# SyncScan_Standalone_MK3_SMD.net
KiCad netlist of a schematic drawn in EAGLE
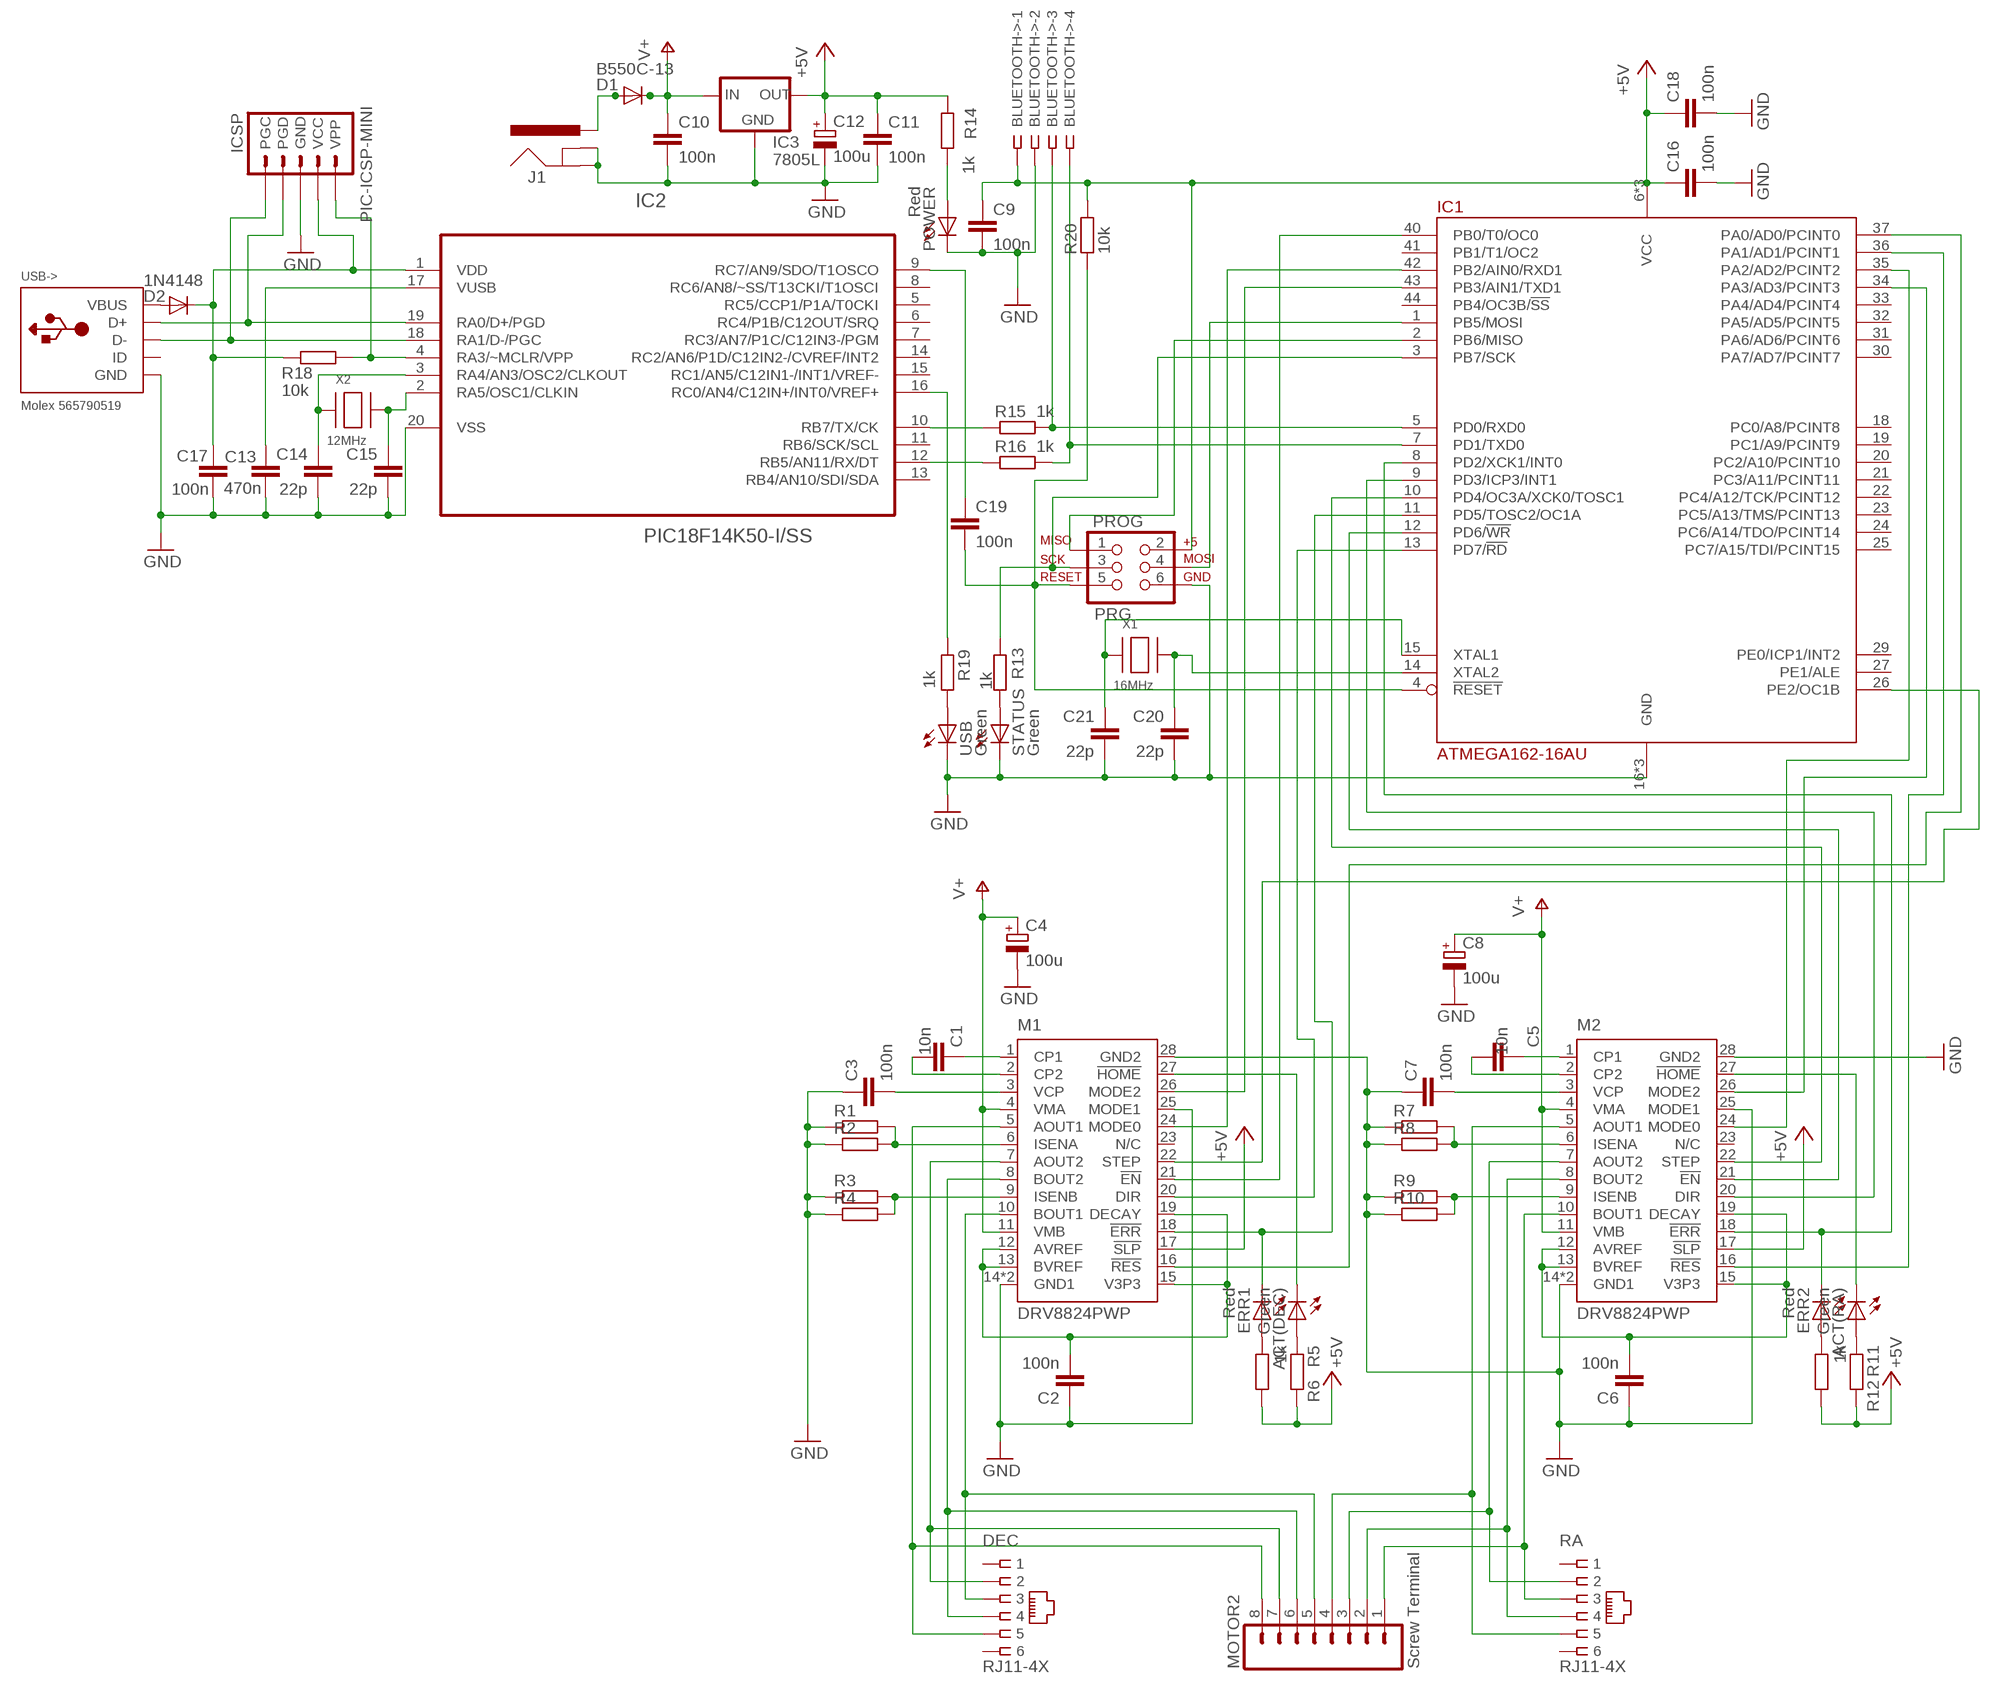
[diagram p0: schematic, sheet 1]

(export (version "E")
  (design (tool "Eeschema 10.0.6"))
  (components
    (comp (ref "ACT(DEC)")
      (value "Green")
      (footprint "eagle-import:1206")
      (fields (field (name "MF") "KINGBRIGHT") (field (name "MPN") "L-424GDT"))
      (libsource (lib "eagle-import") (part "LEDSMT1206"))
    )
    (comp (ref "ACT(RA)")
      (value "Green")
      (footprint "eagle-import:1206")
      (fields (field (name "MF") "KINGBRIGHT") (field (name "MPN") "L-424GDT"))
      (libsource (lib "eagle-import") (part "LEDSMT1206"))
    )
    (comp (ref "BLUETOOTH->")
      (value "http://www.ebay.co.uk/itm/250991624201")
      (footprint "eagle-import:SSW-104-02-S-S-RA")
      (fields (field (name "MPN") "SSW-104-02-S-S-RA") (field (name "OC_FARNELL") "unknown"))
      (libsource (lib "eagle-import") (part "SSW-104-02-S-S-RA"))
    )
    (comp (ref "C1")
      (value "10n")
      (footprint "eagle-import:C0603K")
      (fields (field (name "MF") "KEMET") (field (name "MPN") "C0603C103K1RACTU"))
      (libsource (lib "eagle-import") (part "resistor_C-EUC0603K"))
    )
    (comp (ref "C2")
      (value "100n")
      (footprint "eagle-import:C0603K")
      (fields (field (name "MF") "KEMET") (field (name "MPN") "C0603C104K4RACTU"))
      (libsource (lib "eagle-import") (part "resistor_C-EUC0603K"))
    )
    (comp (ref "C3")
      (value "100n")
      (footprint "eagle-import:C0603K")
      (fields (field (name "MF") "KEMET") (field (name "MPN") "C0603C104K4RACTU"))
      (libsource (lib "eagle-import") (part "resistor_C-EUC0603K"))
    )
    (comp (ref "C4")
      (value "100u")
      (footprint "eagle-import:E2,5-6")
      (fields (field (name "MF") "MULTICOMP") (field (name "MPN") "MCGPR25V107M6.3X11"))
      (libsource (lib "eagle-import") (part "CPOL-EUE2.5-6"))
    )
    (comp (ref "C5")
      (value "10n")
      (footprint "eagle-import:C0603K")
      (fields (field (name "MF") "KEMET") (field (name "MPN") "C0603C103K1RACTU"))
      (libsource (lib "eagle-import") (part "resistor_C-EUC0603K"))
    )
    (comp (ref "C6")
      (value "100n")
      (footprint "eagle-import:C0603K")
      (fields (field (name "MF") "KEMET") (field (name "MPN") "C0603C104K4RACTU"))
      (libsource (lib "eagle-import") (part "resistor_C-EUC0603K"))
    )
    (comp (ref "C7")
      (value "100n")
      (footprint "eagle-import:C0603K")
      (fields (field (name "MF") "KEMET") (field (name "MPN") "C0603C104K4RACTU"))
      (libsource (lib "eagle-import") (part "resistor_C-EUC0603K"))
    )
    (comp (ref "C8")
      (value "100u")
      (footprint "eagle-import:E2,5-6")
      (fields (field (name "MF") "MULTICOMP") (field (name "MPN") "MCGPR25V107M6.3X11"))
      (libsource (lib "eagle-import") (part "CPOL-EUE2.5-6"))
    )
    (comp (ref "C9")
      (value "100n")
      (footprint "eagle-import:C0603K")
      (fields (field (name "MF") "KEMET") (field (name "MPN") "C0603C104K4RACTU"))
      (libsource (lib "eagle-import") (part "resistor_C-EUC0603K"))
    )
    (comp (ref "C10")
      (value "100n")
      (footprint "eagle-import:C0603K")
      (fields (field (name "MF") "KEMET") (field (name "MPN") "C0603C104K4RACTU"))
      (libsource (lib "eagle-import") (part "resistor_C-EUC0603K"))
    )
    (comp (ref "C11")
      (value "100n")
      (footprint "eagle-import:C0603K")
      (fields (field (name "MF") "KEMET") (field (name "MPN") "C0603C104K4RACTU"))
      (libsource (lib "eagle-import") (part "resistor_C-EUC0603K"))
    )
    (comp (ref "C12")
      (value "100u")
      (footprint "eagle-import:E2,5-6")
      (fields (field (name "MF") "MULTICOMP") (field (name "MPN") "MCGPR25V107M6.3X11"))
      (libsource (lib "eagle-import") (part "CPOL-EUE2.5-6"))
    )
    (comp (ref "C13")
      (value "470n")
      (footprint "eagle-import:C0603K")
      (fields (field (name "MF") "AVX") (field (name "MPN") "0603ZD474KAT2A"))
      (libsource (lib "eagle-import") (part "C-EUC0603K"))
    )
    (comp (ref "C14")
      (value "22p")
      (footprint "eagle-import:C0603K")
      (fields (field (name "MF") "MULTICOMP") (field (name "MPN") "U0603C220JCT"))
      (libsource (lib "eagle-import") (part "C-EUC0603K"))
    )
    (comp (ref "C15")
      (value "22p")
      (footprint "eagle-import:C0603K")
      (fields (field (name "MF") "MULTICOMP") (field (name "MPN") "U0603C220JCT"))
      (libsource (lib "eagle-import") (part "C-EUC0603K"))
    )
    (comp (ref "C16")
      (value "100n")
      (footprint "eagle-import:C0603K")
      (fields (field (name "MF") "KEMET") (field (name "MPN") "C0603C104K4RACTU"))
      (libsource (lib "eagle-import") (part "resistor_C-EUC0603K"))
    )
    (comp (ref "C17")
      (value "100n")
      (footprint "eagle-import:C0603K")
      (fields (field (name "MF") "KEMET") (field (name "MPN") "C0603C104K4RACTU"))
      (libsource (lib "eagle-import") (part "resistor_C-EUC0603K"))
    )
    (comp (ref "C18")
      (value "100n")
      (footprint "eagle-import:C0603K")
      (fields (field (name "MF") "KEMET") (field (name "MPN") "C0603C104K4RACTU"))
      (libsource (lib "eagle-import") (part "resistor_C-EUC0603K"))
    )
    (comp (ref "C19")
      (value "100n")
      (footprint "eagle-import:C0603K")
      (fields (field (name "MF") "KEMET") (field (name "MPN") "C0603C104K4RACTU"))
      (libsource (lib "eagle-import") (part "resistor_C-EUC0603K"))
    )
    (comp (ref "C20")
      (value "22p")
      (footprint "eagle-import:C0603K")
      (fields (field (name "MF") "MULTICOMP") (field (name "MPN") "U0603C220JCT"))
      (libsource (lib "eagle-import") (part "C-EUC0603K"))
    )
    (comp (ref "C21")
      (value "22p")
      (footprint "eagle-import:C0603K")
      (fields (field (name "MF") "MULTICOMP") (field (name "MPN") "U0603C220JCT"))
      (libsource (lib "eagle-import") (part "C-EUC0603K"))
    )
    (comp (ref "D1")
      (value "B550C-13")
      (footprint "eagle-import:SMC")
      (fields (field (name "MF") "DIODES INC.") (field (name "MPN") "B550C-13-F"))
      (libsource (lib "eagle-import") (part "DIODE-SMC"))
    )
    (comp (ref "D2")
      (value "1N4148")
      (footprint "eagle-import:SOD-323")
      (fields (field (name "MF") "MULTICOMP") (field (name "MPN") "1N4148."))
      (libsource (lib "eagle-import") (part "DIODESOD"))
    )
    (comp (ref "DEC")
      (value "RJ11-4X")
      (footprint "eagle-import:RJ11-NO_SHIELD")
      (fields
        (field (name "MPN") "6609214-3")
        (field (name "MF") "MH CONNECTORS")
        (field (name "MPN_1") "MHRJJ64NFRA")
        (field (name "OC_FARNELL") "3938347")
      )
      (libsource (lib "eagle-import") (part "RJ11-4X"))
    )
    (comp (ref "ERR1")
      (value "Red")
      (footprint "eagle-import:1206")
      (fields (field (name "MF") "KINGBRIGHT") (field (name "MPN") "L-424HDT"))
      (libsource (lib "eagle-import") (part "LEDSMT1206"))
    )
    (comp (ref "ERR2")
      (value "Red")
      (footprint "eagle-import:1206")
      (fields (field (name "MF") "KINGBRIGHT") (field (name "MPN") "L-424HDT"))
      (libsource (lib "eagle-import") (part "LEDSMT1206"))
    )
    (comp (ref "IC1")
      (value "ATMEGA162-16AU")
      (footprint "eagle-import:TQFP44")
      (fields (field (name "MF") "ATMEL"))
      (libsource (lib "eagle-import") (part "ATMEGA162-16AU"))
    )
    (comp (ref "IC2")
      (value "PIC18F14K50-I/SS")
      (footprint "eagle-import:SSOP20")
      (fields (field (name "MF") "MICROCHIP"))
      (libsource (lib "eagle-import") (part "PIC18F14K50-I/SS"))
    )
    (comp (ref "IC3")
      (value "7805L")
      (footprint "eagle-import:SOT23")
      (fields (field (name "MF") "TAIWAN SEMICONDUCTOR") (field (name "MPN") "TS78L05CX RF"))
      (libsource (lib "eagle-import") (part "78LXXSOT-23"))
    )
    (comp (ref "ICSP")
      (value "PIC-ICSP-MINI")
      (footprint "eagle-import:PIC-ICSP-MINI")
      (libsource (lib "eagle-import") (part "PIC-ICSP-MINI"))
    )
    (comp (ref "J1")
      (value "POWER_JACKSMD")
      (footprint "eagle-import:POWER_JACK_SMD")
      (fields (field (name "MF") "MULTICOMP") (field (name "MPN") "MJ-179SMT"))
      (libsource (lib "eagle-import") (part "POWER_JACKSMD"))
    )
    (comp (ref "M1")
      (value "DRV8824PWP")
      (footprint "eagle-import:HTSSOP28PWP")
      (fields (field (name "MF") "TEXAS INSTRUMENTS"))
      (libsource (lib "eagle-import") (part "DRV8824PWP"))
    )
    (comp (ref "M2")
      (value "DRV8824PWP")
      (footprint "eagle-import:HTSSOP28PWP")
      (fields (field (name "MF") "TEXAS INSTRUMENTS"))
      (libsource (lib "eagle-import") (part "DRV8824PWP"))
    )
    (comp (ref "MOTOR2")
      (value "Screw Terminal")
      (footprint "eagle-import:SCREWTERMINAL-3.5MM-8")
      (fields (field (name "MF") "LUMBERG") (field (name "MPN") "KRMC 08"))
      (libsource (lib "eagle-import") (part "M083.5MM-8"))
    )
    (comp (ref "POWER")
      (value "Red")
      (footprint "eagle-import:1206")
      (fields (field (name "MF") "KINGBRIGHT") (field (name "MPN") "L-424HDT"))
      (libsource (lib "eagle-import") (part "LEDSMT1206"))
    )
    (comp (ref "PROG")
      (value "PRG")
      (footprint "eagle-import:2X3")
      (fields (field (name "MF") "TE CONNECTIVITY / AMP") (field (name "MPN") "826632-3"))
      (libsource (lib "eagle-import") (part "AVR_SPI_PRG_6PTH"))
    )
    (comp (ref "R1")
      (value "1.5R")
      (footprint "eagle-import:R2512")
      (fields (field (name "MF") "YAGEO (PHYCOMP)") (field (name "MPN") "RC2512FK-7W1R5L"))
      (libsource (lib "eagle-import") (part "resistor_R-EU_R2512"))
    )
    (comp (ref "R2")
      (value "1.5R")
      (footprint "eagle-import:R2512")
      (fields (field (name "MF") "YAGEO (PHYCOMP)") (field (name "MPN") "RC2512FK-7W1R5L"))
      (libsource (lib "eagle-import") (part "resistor_R-EU_R2512"))
    )
    (comp (ref "R3")
      (value "1.5R")
      (footprint "eagle-import:R2512")
      (fields (field (name "MF") "YAGEO (PHYCOMP)") (field (name "MPN") "RC2512FK-7W1R5L"))
      (libsource (lib "eagle-import") (part "resistor_R-EU_R2512"))
    )
    (comp (ref "R4")
      (value "1.5R")
      (footprint "eagle-import:R2512")
      (fields (field (name "MF") "YAGEO (PHYCOMP)") (field (name "MPN") "RC2512FK-7W1R5L"))
      (libsource (lib "eagle-import") (part "resistor_R-EU_R2512"))
    )
    (comp (ref "R5")
      (value "1k")
      (footprint "eagle-import:R0603")
      (fields (field (name "MF") "VISHAY DRALORIC") (field (name "MPN") "CRCW06031K00FKEA"))
      (libsource (lib "eagle-import") (part "resistor_R-EU_R0603"))
    )
    (comp (ref "R6")
      (value "1k")
      (footprint "eagle-import:R0603")
      (fields (field (name "MF") "VISHAY DRALORIC") (field (name "MPN") "CRCW06031K00FKEA"))
      (libsource (lib "eagle-import") (part "resistor_R-EU_R0603"))
    )
    (comp (ref "R7")
      (value "1.5R")
      (footprint "eagle-import:R2512")
      (fields (field (name "MF") "YAGEO (PHYCOMP)") (field (name "MPN") "RC2512FK-7W1R5L"))
      (libsource (lib "eagle-import") (part "resistor_R-EU_R2512"))
    )
    (comp (ref "R8")
      (value "1.5R")
      (footprint "eagle-import:R2512")
      (fields (field (name "MF") "YAGEO (PHYCOMP)") (field (name "MPN") "RC2512FK-7W1R5L"))
      (libsource (lib "eagle-import") (part "resistor_R-EU_R2512"))
    )
    (comp (ref "R9")
      (value "1.5R")
      (footprint "eagle-import:R2512")
      (fields (field (name "MF") "YAGEO (PHYCOMP)") (field (name "MPN") "RC2512FK-7W1R5L"))
      (libsource (lib "eagle-import") (part "resistor_R-EU_R2512"))
    )
    (comp (ref "R10")
      (value "1.5R")
      (footprint "eagle-import:R2512")
      (fields (field (name "MF") "YAGEO (PHYCOMP)") (field (name "MPN") "RC2512FK-7W1R5L"))
      (libsource (lib "eagle-import") (part "resistor_R-EU_R2512"))
    )
    (comp (ref "R11")
      (value "1k")
      (footprint "eagle-import:R0603")
      (fields (field (name "MF") "VISHAY DRALORIC") (field (name "MPN") "CRCW06031K00FKEA"))
      (libsource (lib "eagle-import") (part "resistor_R-EU_R0603"))
    )
    (comp (ref "R12")
      (value "1k")
      (footprint "eagle-import:R0603")
      (fields (field (name "MF") "VISHAY DRALORIC") (field (name "MPN") "CRCW06031K00FKEA"))
      (libsource (lib "eagle-import") (part "resistor_R-EU_R0603"))
    )
    (comp (ref "R13")
      (value "1k")
      (footprint "eagle-import:R0603")
      (fields (field (name "MF") "VISHAY DRALORIC") (field (name "MPN") "CRCW06031K00FKEA"))
      (libsource (lib "eagle-import") (part "rcl_R-EU_R0603"))
    )
    (comp (ref "R14")
      (value "1k")
      (footprint "eagle-import:R0603")
      (fields (field (name "MF") "VISHAY DRALORIC") (field (name "MPN") "CRCW06031K00FKEA"))
      (libsource (lib "eagle-import") (part "rcl_R-EU_R0603"))
    )
    (comp (ref "R15")
      (value "1k")
      (footprint "eagle-import:R0603")
      (fields (field (name "MF") "VISHAY DRALORIC") (field (name "MPN") "CRCW06031K00FKEA"))
      (libsource (lib "eagle-import") (part "R-EU_R0603"))
    )
    (comp (ref "R16")
      (value "1k")
      (footprint "eagle-import:R0603")
      (fields (field (name "MF") "VISHAY DRALORIC") (field (name "MPN") "CRCW06031K00FKEA"))
      (libsource (lib "eagle-import") (part "R-EU_R0603"))
    )
    (comp (ref "R18")
      (value "10k")
      (footprint "eagle-import:R0603")
      (fields (field (name "MF") "VISHAY DRALORIC") (field (name "MPN") "CRCW060310K0FKEA"))
      (libsource (lib "eagle-import") (part "rcl_R-EU_R0603"))
    )
    (comp (ref "R19")
      (value "1k")
      (footprint "eagle-import:R0603")
      (fields (field (name "MF") "VISHAY DRALORIC") (field (name "MPN") "CRCW06031K00FKEA"))
      (libsource (lib "eagle-import") (part "rcl_R-EU_R0603"))
    )
    (comp (ref "R20")
      (value "10k")
      (footprint "eagle-import:R0603")
      (fields (field (name "MF") "VISHAY DRALORIC") (field (name "MPN") "CRCW060310K0FKEA"))
      (libsource (lib "eagle-import") (part "rcl_R-EU_R0603"))
    )
    (comp (ref "RA")
      (value "RJ11-4X")
      (footprint "eagle-import:RJ11-NO_SHIELD")
      (fields
        (field (name "MPN") "6609214-3")
        (field (name "MF") "MH CONNECTORS")
        (field (name "MPN_1") "MHRJJ64NFRA")
        (field (name "OC_FARNELL") "3938347")
      )
      (libsource (lib "eagle-import") (part "RJ11-4X"))
    )
    (comp (ref "STATUS")
      (value "Green")
      (footprint "eagle-import:1206")
      (fields (field (name "MF") "KINGBRIGHT") (field (name "MPN") "L-424GDT"))
      (libsource (lib "eagle-import") (part "LEDSMT1206"))
    )
    (comp (ref "USB")
      (value "Green")
      (footprint "eagle-import:1206")
      (fields (field (name "MF") "KINGBRIGHT") (field (name "MPN") "L-424GDT"))
      (libsource (lib "eagle-import") (part "LEDSMT1206"))
    )
    (comp (ref "USB->")
      (value "Molex 565790519")
      (footprint "eagle-import:USB-MINIB-THM-MOLEX")
      (fields (field (name "MF") "MOLEX") (field (name "MPN") "565790519"))
      (libsource (lib "eagle-import") (part "USBMOLEX"))
    )
    (comp (ref "X1")
      (value "16MHz")
      (footprint "eagle-import:NX5032")
      (fields (field (name "MF") "TXC") (field (name "MPN") "7A-16.000MAAJ-T"))
      (libsource (lib "eagle-import") (part "XTALNX5032"))
    )
    (comp (ref "X2")
      (value "12MHz")
      (footprint "eagle-import:NX5032")
      (fields (field (name "MF") "TXC") (field (name "MPN") "7A-12.000MAAJ-T"))
      (libsource (lib "eagle-import") (part "XTALNX5032"))
    )
  )
  (nets
    (net (code "1") (name "+5V") (class "Default")
      (node (ref "BLUETOOTH->") (pin "1") (pinfunction "1_1") (pintype "passive"))
      (node (ref "C11") (pin "1") (pinfunction "1_1") (pintype "passive"))
      (node (ref "C12") (pin "+") (pinfunction "+_+") (pintype "passive"))
      (node (ref "C16") (pin "1") (pinfunction "1_1") (pintype "passive"))
      (node (ref "C18") (pin "1") (pinfunction "1_1") (pintype "passive"))
      (node (ref "C9") (pin "1") (pinfunction "1_1") (pintype "passive"))
      (node (ref "IC1") (pin "17") (pinfunction "VCC_17") (pintype "power_in"))
      (node (ref "IC1") (pin "38") (pinfunction "VCC_38") (pintype "power_in"))
      (node (ref "IC1") (pin "6") (pinfunction "VCC_6") (pintype "power_in"))
      (node (ref "IC3") (pin "1") (pinfunction "OUT_1") (pintype "passive"))
      (node (ref "M1") (pin "17") (pinfunction "~{SLP}_17") (pintype "input"))
      (node (ref "M2") (pin "17") (pinfunction "~{SLP}_17") (pintype "input"))
      (node (ref "PROG") (pin "2") (pinfunction "2_2") (pintype "passive"))
      (node (ref "R11") (pin "2") (pinfunction "2_2") (pintype "passive"))
      (node (ref "R12") (pin "2") (pinfunction "2_2") (pintype "passive"))
      (node (ref "R14") (pin "1") (pinfunction "1_1") (pintype "passive"))
      (node (ref "R20") (pin "2") (pinfunction "2_2") (pintype "passive"))
      (node (ref "R5") (pin "2") (pinfunction "2_2") (pintype "passive"))
      (node (ref "R6") (pin "2") (pinfunction "2_2") (pintype "passive"))
    )
    (net (code "2") (name "GND") (class "Default")
      (node (ref "BLUETOOTH->") (pin "2") (pinfunction "1_2") (pintype "passive"))
      (node (ref "C10") (pin "2") (pinfunction "2_2") (pintype "passive"))
      (node (ref "C11") (pin "2") (pinfunction "2_2") (pintype "passive"))
      (node (ref "C12") (pin "-") (pinfunction "-_-") (pintype "passive"))
      (node (ref "C13") (pin "1") (pinfunction "1_1") (pintype "passive"))
      (node (ref "C14") (pin "2") (pinfunction "2_2") (pintype "passive"))
      (node (ref "C15") (pin "2") (pinfunction "2_2") (pintype "passive"))
      (node (ref "C16") (pin "2") (pinfunction "2_2") (pintype "passive"))
      (node (ref "C17") (pin "2") (pinfunction "2_2") (pintype "passive"))
      (node (ref "C18") (pin "2") (pinfunction "2_2") (pintype "passive"))
      (node (ref "C2") (pin "1") (pinfunction "1_1") (pintype "passive"))
      (node (ref "C20") (pin "2") (pinfunction "2_2") (pintype "passive"))
      (node (ref "C21") (pin "2") (pinfunction "2_2") (pintype "passive"))
      (node (ref "C3") (pin "1") (pinfunction "1_1") (pintype "passive"))
      (node (ref "C4") (pin "-") (pinfunction "-_-") (pintype "passive"))
      (node (ref "C6") (pin "1") (pinfunction "1_1") (pintype "passive"))
      (node (ref "C7") (pin "1") (pinfunction "1_1") (pintype "passive"))
      (node (ref "C8") (pin "-") (pinfunction "-_-") (pintype "passive"))
      (node (ref "C9") (pin "2") (pinfunction "2_2") (pintype "passive"))
      (node (ref "IC1") (pin "16") (pinfunction "GND_16") (pintype "power_in"))
      (node (ref "IC1") (pin "28") (pinfunction "GND_28") (pintype "power_in"))
      (node (ref "IC1") (pin "39") (pinfunction "GND_39") (pintype "power_in"))
      (node (ref "IC2") (pin "20") (pinfunction "VSS_20") (pintype "power_in"))
      (node (ref "IC3") (pin "3") (pinfunction "GND_3") (pintype "input"))
      (node (ref "ICSP") (pin "3") (pinfunction "GND_3") (pintype "passive"))
      (node (ref "J1") (pin "GND") (pinfunction "GNDBREAK_GND") (pintype "bidirectional"))
      (node (ref "J1") (pin "P$4") (pinfunction "GND_P$4") (pintype "bidirectional"))
      (node (ref "M1") (pin "14") (pinfunction "GND1_14") (pintype "power_in"))
      (node (ref "M1") (pin "25") (pinfunction "MODE1_25") (pintype "input"))
      (node (ref "M1") (pin "28") (pinfunction "GND2_28") (pintype "power_in"))
      (node (ref "M1") (pin "EXP") (pinfunction "GND1_EXP") (pintype "power_in"))
      (node (ref "M2") (pin "14") (pinfunction "GND1_14") (pintype "power_in"))
      (node (ref "M2") (pin "25") (pinfunction "MODE1_25") (pintype "input"))
      (node (ref "M2") (pin "28") (pinfunction "GND2_28") (pintype "power_in"))
      (node (ref "M2") (pin "EXP") (pinfunction "GND1_EXP") (pintype "power_in"))
      (node (ref "POWER") (pin "C") (pinfunction "C_C") (pintype "passive"))
      (node (ref "PROG") (pin "6") (pinfunction "6_6") (pintype "passive"))
      (node (ref "R1") (pin "1") (pinfunction "1_1") (pintype "passive"))
      (node (ref "R10") (pin "1") (pinfunction "1_1") (pintype "passive"))
      (node (ref "R2") (pin "1") (pinfunction "1_1") (pintype "passive"))
      (node (ref "R3") (pin "1") (pinfunction "1_1") (pintype "passive"))
      (node (ref "R4") (pin "1") (pinfunction "1_1") (pintype "passive"))
      (node (ref "R7") (pin "1") (pinfunction "1_1") (pintype "passive"))
      (node (ref "R8") (pin "1") (pinfunction "1_1") (pintype "passive"))
      (node (ref "R9") (pin "1") (pinfunction "1_1") (pintype "passive"))
      (node (ref "STATUS") (pin "C") (pinfunction "C_C") (pintype "passive"))
      (node (ref "USB") (pin "C") (pinfunction "C_C") (pintype "passive"))
      (node (ref "USB->") (pin "GND") (pinfunction "GND_GND") (pintype "power_in"))
    )
    (net (code "3") (name "Net-(ACT(DEC)-PadA)") (class "Default")
      (node (ref "ACT(DEC)") (pin "A") (pinfunction "A_A") (pintype "passive"))
      (node (ref "R5") (pin "1") (pinfunction "1_1") (pintype "passive"))
    )
    (net (code "4") (name "Net-(ACT(RA)-PadA)") (class "Default")
      (node (ref "ACT(RA)") (pin "A") (pinfunction "A_A") (pintype "passive"))
      (node (ref "R11") (pin "1") (pinfunction "1_1") (pintype "passive"))
    )
    (net (code "5") (name "Net-(BLUETOOTH->C-1)") (class "Default")
      (node (ref "BLUETOOTH->") (pin "3") (pinfunction "1_3") (pintype "passive"))
      (node (ref "IC1") (pin "5") (pinfunction "PD0/RXD0_5") (pintype "bidirectional"))
      (node (ref "R15") (pin "1") (pinfunction "1_1") (pintype "passive"))
    )
    (net (code "6") (name "Net-(BLUETOOTH->D-1)") (class "Default")
      (node (ref "BLUETOOTH->") (pin "4") (pinfunction "1_4") (pintype "passive"))
      (node (ref "IC1") (pin "7") (pinfunction "PD1/TXD0_7") (pintype "bidirectional"))
      (node (ref "R16") (pin "1") (pinfunction "1_1") (pintype "passive"))
    )
    (net (code "7") (name "Net-(D1-PadA)") (class "Default")
      (node (ref "D1") (pin "A") (pinfunction "A_A") (pintype "passive"))
      (node (ref "J1") (pin "VIN0") (pinfunction "PWR_VIN0") (pintype "bidirectional"))
      (node (ref "J1") (pin "VIN1") (pinfunction "PWR_VIN1") (pintype "bidirectional"))
    )
    (net (code "8") (name "Net-(D2-A)") (class "Default")
      (node (ref "D2") (pin "2") (pinfunction "A_2") (pintype "passive"))
      (node (ref "USB->") (pin "VBUS") (pinfunction "VBUS_VBUS") (pintype "power_in"))
    )
    (net (code "9") (name "Net-(D2-C)") (class "Default")
      (node (ref "C17") (pin "1") (pinfunction "1_1") (pintype "passive"))
      (node (ref "D2") (pin "1") (pinfunction "C_1") (pintype "passive"))
      (node (ref "IC2") (pin "1") (pinfunction "VDD_1") (pintype "power_in"))
      (node (ref "ICSP") (pin "2") (pinfunction "VCC_2") (pintype "passive"))
      (node (ref "R18") (pin "2") (pinfunction "2_2") (pintype "passive"))
    )
    (net (code "10") (name "Net-(ERR1-PadA)") (class "Default")
      (node (ref "ERR1") (pin "A") (pinfunction "A_A") (pintype "passive"))
      (node (ref "R6") (pin "1") (pinfunction "1_1") (pintype "passive"))
    )
    (net (code "11") (name "Net-(ERR2-PadA)") (class "Default")
      (node (ref "ERR2") (pin "A") (pinfunction "A_A") (pintype "passive"))
      (node (ref "R12") (pin "1") (pinfunction "1_1") (pintype "passive"))
    )
    (net (code "12") (name "Net-(IC1-PA0{slash}AD0{slash}PCINT0)") (class "Default")
      (node (ref "IC1") (pin "37") (pinfunction "PA0/AD0/PCINT0_37") (pintype "bidirectional"))
      (node (ref "M1") (pin "16") (pinfunction "~{RES}_16") (pintype "input"))
    )
    (net (code "13") (name "Net-(IC1-PA1{slash}AD1{slash}PCINT1)") (class "Default")
      (node (ref "IC1") (pin "36") (pinfunction "PA1/AD1/PCINT1_36") (pintype "bidirectional"))
      (node (ref "M2") (pin "16") (pinfunction "~{RES}_16") (pintype "input"))
    )
    (net (code "14") (name "Net-(IC1-PA2{slash}AD2{slash}PCINT2)") (class "Default")
      (node (ref "IC1") (pin "35") (pinfunction "PA2/AD2/PCINT2_35") (pintype "bidirectional"))
      (node (ref "M2") (pin "24") (pinfunction "MODE0_24") (pintype "input"))
    )
    (net (code "15") (name "Net-(IC1-PA3{slash}AD3{slash}PCINT3)") (class "Default")
      (node (ref "IC1") (pin "34") (pinfunction "PA3/AD3/PCINT3_34") (pintype "bidirectional"))
      (node (ref "M2") (pin "26") (pinfunction "MODE2_26") (pintype "input"))
    )
    (net (code "16") (name "Net-(IC1-PB0{slash}T0{slash}OC0)") (class "Default")
      (node (ref "IC1") (pin "40") (pinfunction "PB0/T0/OC0_40") (pintype "bidirectional"))
      (node (ref "M1") (pin "21") (pinfunction "~{EN}_21") (pintype "input"))
    )
    (net (code "17") (name "Net-(IC1-PB2{slash}AIN0{slash}RXD1)") (class "Default")
      (node (ref "IC1") (pin "42") (pinfunction "PB2/AIN0/RXD1_42") (pintype "bidirectional"))
      (node (ref "M1") (pin "24") (pinfunction "MODE0_24") (pintype "input"))
    )
    (net (code "18") (name "Net-(IC1-PB3{slash}AIN1{slash}TXD1)") (class "Default")
      (node (ref "IC1") (pin "43") (pinfunction "PB3/AIN1/TXD1_43") (pintype "bidirectional"))
      (node (ref "M1") (pin "26") (pinfunction "MODE2_26") (pintype "input"))
    )
    (net (code "19") (name "Net-(IC1-PB5{slash}MOSI)") (class "Default")
      (node (ref "IC1") (pin "1") (pinfunction "PB5/MOSI_1") (pintype "bidirectional"))
      (node (ref "PROG") (pin "4") (pinfunction "4_4") (pintype "passive"))
    )
    (net (code "20") (name "Net-(IC1-PB6{slash}MISO)") (class "Default")
      (node (ref "IC1") (pin "2") (pinfunction "PB6/MISO_2") (pintype "bidirectional"))
      (node (ref "PROG") (pin "1") (pinfunction "1_1") (pintype "passive"))
    )
    (net (code "21") (name "Net-(IC1-PB7{slash}SCK)") (class "Default")
      (node (ref "IC1") (pin "3") (pinfunction "PB7/SCK_3") (pintype "bidirectional"))
      (node (ref "PROG") (pin "3") (pinfunction "3_3") (pintype "passive"))
      (node (ref "R13") (pin "1") (pinfunction "1_1") (pintype "passive"))
    )
    (net (code "22") (name "Net-(IC1-PD2{slash}XCK1{slash}INT0)") (class "Default")
      (node (ref "ERR2") (pin "C") (pinfunction "C_C") (pintype "passive"))
      (node (ref "IC1") (pin "8") (pinfunction "PD2/XCK1/INT0_8") (pintype "bidirectional"))
      (node (ref "M2") (pin "18") (pinfunction "~{ERR}_18") (pintype "output"))
    )
    (net (code "23") (name "Net-(IC1-PD3{slash}ICP3{slash}INT1)") (class "Default")
      (node (ref "IC1") (pin "9") (pinfunction "PD3/ICP3/INT1_9") (pintype "bidirectional"))
      (node (ref "M2") (pin "20") (pinfunction "DIR_20") (pintype "input"))
    )
    (net (code "24") (name "Net-(IC1-PD4{slash}OC3A{slash}XCK0{slash}TOSC1)") (class "Default")
      (node (ref "IC1") (pin "10") (pinfunction "PD4/OC3A/XCK0/TOSC1_10") (pintype "bidirectional"))
      (node (ref "M2") (pin "22") (pinfunction "STEP_22") (pintype "input"))
    )
    (net (code "25") (name "Net-(IC1-PD5{slash}TOSC2{slash}OC1A)") (class "Default")
      (node (ref "ERR1") (pin "C") (pinfunction "C_C") (pintype "passive"))
      (node (ref "IC1") (pin "11") (pinfunction "PD5/TOSC2/OC1A_11") (pintype "bidirectional"))
      (node (ref "M1") (pin "18") (pinfunction "~{ERR}_18") (pintype "output"))
    )
    (net (code "26") (name "Net-(IC1-PD6{slash}~{WR})") (class "Default")
      (node (ref "IC1") (pin "12") (pinfunction "PD6/~{WR}_12") (pintype "bidirectional"))
      (node (ref "M2") (pin "21") (pinfunction "~{EN}_21") (pintype "input"))
    )
    (net (code "27") (name "Net-(IC1-PD7{slash}~{RD})") (class "Default")
      (node (ref "IC1") (pin "13") (pinfunction "PD7/~{RD}_13") (pintype "bidirectional"))
      (node (ref "M1") (pin "20") (pinfunction "DIR_20") (pintype "input"))
    )
    (net (code "28") (name "Net-(IC1-PE2{slash}OC1B)") (class "Default")
      (node (ref "IC1") (pin "26") (pinfunction "PE2/OC1B_26") (pintype "bidirectional"))
      (node (ref "M1") (pin "22") (pinfunction "STEP_22") (pintype "input"))
    )
    (net (code "29") (name "Net-(IC1-XTAL1)") (class "Default")
      (node (ref "C21") (pin "1") (pinfunction "1_1") (pintype "passive"))
      (node (ref "IC1") (pin "15") (pinfunction "XTAL1_15") (pintype "input"))
      (node (ref "X1") (pin "P$1") (pinfunction "P$1_P$1") (pintype "bidirectional"))
    )
    (net (code "30") (name "Net-(IC1-XTAL2)") (class "Default")
      (node (ref "C20") (pin "1") (pinfunction "1_1") (pintype "passive"))
      (node (ref "IC1") (pin "14") (pinfunction "XTAL2_14") (pintype "input"))
      (node (ref "X1") (pin "P$2") (pinfunction "P$2_P$2") (pintype "bidirectional"))
    )
    (net (code "31") (name "Net-(IC1-~{RESET})") (class "Default")
      (node (ref "C19") (pin "2") (pinfunction "2_2") (pintype "passive"))
      (node (ref "IC1") (pin "4") (pinfunction "~{RESET}_4") (pintype "input"))
      (node (ref "PROG") (pin "5") (pinfunction "5_5") (pintype "passive"))
      (node (ref "R20") (pin "1") (pinfunction "1_1") (pintype "passive"))
    )
    (net (code "32") (name "Net-(IC2-RA0{slash}D+{slash}PGD)") (class "Default")
      (node (ref "IC2") (pin "19") (pinfunction "RA0/D+/PGD_19") (pintype "bidirectional"))
      (node (ref "ICSP") (pin "4") (pinfunction "PGD_4") (pintype "passive"))
      (node (ref "USB->") (pin "D+") (pinfunction "D+_D+") (pintype "bidirectional"))
    )
    (net (code "33") (name "Net-(IC2-RA1{slash}D-{slash}PGC)") (class "Default")
      (node (ref "IC2") (pin "18") (pinfunction "RA1/D-/PGC_18") (pintype "bidirectional"))
      (node (ref "ICSP") (pin "5") (pinfunction "PGC_5") (pintype "passive"))
      (node (ref "USB->") (pin "D-") (pinfunction "D-_D-") (pintype "bidirectional"))
    )
    (net (code "34") (name "Net-(IC2-RA3{slash}~{MCLR{slash}VPP})") (class "Default")
      (node (ref "IC2") (pin "4") (pinfunction "RA3/~{MCLR/VPP}_4") (pintype "input"))
      (node (ref "ICSP") (pin "1") (pinfunction "VPP_1") (pintype "passive"))
      (node (ref "R18") (pin "1") (pinfunction "1_1") (pintype "passive"))
    )
    (net (code "35") (name "Net-(IC2-RA4{slash}AN3{slash}OSC2{slash}CLKOUT)") (class "Default")
      (node (ref "C14") (pin "1") (pinfunction "1_1") (pintype "passive"))
      (node (ref "IC2") (pin "3") (pinfunction "RA4/AN3/OSC2/CLKOUT_3") (pintype "bidirectional"))
      (node (ref "X2") (pin "P$1") (pinfunction "P$1_P$1") (pintype "bidirectional"))
    )
    (net (code "36") (name "Net-(IC2-RA5{slash}OSC1{slash}CLKIN)") (class "Default")
      (node (ref "C15") (pin "1") (pinfunction "1_1") (pintype "passive"))
      (node (ref "IC2") (pin "2") (pinfunction "RA5/OSC1/CLKIN_2") (pintype "bidirectional"))
      (node (ref "X2") (pin "P$2") (pinfunction "P$2_P$2") (pintype "bidirectional"))
    )
    (net (code "37") (name "Net-(IC2-RB5{slash}AN11{slash}RX{slash}DT)") (class "Default")
      (node (ref "IC2") (pin "12") (pinfunction "RB5/AN11/RX/DT_12") (pintype "bidirectional"))
      (node (ref "R16") (pin "2") (pinfunction "2_2") (pintype "passive"))
    )
    (net (code "38") (name "Net-(IC2-RB7{slash}TX{slash}CK)") (class "Default")
      (node (ref "IC2") (pin "10") (pinfunction "RB7/TX/CK_10") (pintype "bidirectional"))
      (node (ref "R15") (pin "2") (pinfunction "2_2") (pintype "passive"))
    )
    (net (code "39") (name "Net-(IC2-RC0{slash}AN4{slash}C12IN+{slash}INT0{slash}VREF+)") (class "Default")
      (node (ref "IC2") (pin "16") (pinfunction "RC0/AN4/C12IN+/INT0/VREF+_16") (pintype "bidirectional"))
      (node (ref "R19") (pin "2") (pinfunction "2_2") (pintype "passive"))
    )
    (net (code "40") (name "Net-(IC2-RC7{slash}AN9{slash}SDO{slash}T1OSCO)") (class "Default")
      (node (ref "C19") (pin "1") (pinfunction "1_1") (pintype "passive"))
      (node (ref "IC2") (pin "9") (pinfunction "RC7/AN9/SDO/T1OSCO_9") (pintype "bidirectional"))
    )
    (net (code "41") (name "Net-(IC2-VUSB)") (class "Default")
      (node (ref "C13") (pin "2") (pinfunction "2_2") (pintype "passive"))
      (node (ref "IC2") (pin "17") (pinfunction "VUSB_17") (pintype "power_in"))
    )
    (net (code "42") (name "Net-(M1-AOUT1)") (class "Default")
      (node (ref "DEC") (pin "5") (pinfunction "5_5") (pintype "passive"))
      (node (ref "M1") (pin "5") (pinfunction "AOUT1_5") (pintype "output"))
      (node (ref "MOTOR2") (pin "8") (pinfunction "8_8") (pintype "passive"))
    )
    (net (code "43") (name "Net-(M1-AOUT2)") (class "Default")
      (node (ref "DEC") (pin "2") (pinfunction "2_2") (pintype "passive"))
      (node (ref "M1") (pin "7") (pinfunction "AOUT2_7") (pintype "output"))
      (node (ref "MOTOR2") (pin "7") (pinfunction "7_7") (pintype "passive"))
    )
    (net (code "44") (name "Net-(M1-AVREF)") (class "Default")
      (node (ref "C2") (pin "2") (pinfunction "2_2") (pintype "passive"))
      (node (ref "M1") (pin "12") (pinfunction "AVREF_12") (pintype "input"))
      (node (ref "M1") (pin "13") (pinfunction "BVREF_13") (pintype "input"))
      (node (ref "M1") (pin "15") (pinfunction "V3P3_15") (pintype "output"))
      (node (ref "M1") (pin "19") (pinfunction "DECAY_19") (pintype "input"))
    )
    (net (code "45") (name "Net-(M1-BOUT1)") (class "Default")
      (node (ref "DEC") (pin "3") (pinfunction "3_3") (pintype "passive"))
      (node (ref "M1") (pin "10") (pinfunction "BOUT1_10") (pintype "output"))
      (node (ref "MOTOR2") (pin "5") (pinfunction "5_5") (pintype "passive"))
    )
    (net (code "46") (name "Net-(M1-BOUT2)") (class "Default")
      (node (ref "DEC") (pin "4") (pinfunction "4_4") (pintype "passive"))
      (node (ref "M1") (pin "8") (pinfunction "BOUT2_8") (pintype "output"))
      (node (ref "MOTOR2") (pin "6") (pinfunction "6_6") (pintype "passive"))
    )
    (net (code "47") (name "Net-(M1-CP1)") (class "Default")
      (node (ref "C1") (pin "1") (pinfunction "1_1") (pintype "passive"))
      (node (ref "M1") (pin "1") (pinfunction "CP1_1") (pintype "passive"))
    )
    (net (code "48") (name "Net-(M1-CP2)") (class "Default")
      (node (ref "C1") (pin "2") (pinfunction "2_2") (pintype "passive"))
      (node (ref "M1") (pin "2") (pinfunction "CP2_2") (pintype "passive"))
    )
    (net (code "49") (name "Net-(M1-ISENA)") (class "Default")
      (node (ref "M1") (pin "6") (pinfunction "ISENA_6") (pintype "bidirectional"))
      (node (ref "R1") (pin "2") (pinfunction "2_2") (pintype "passive"))
      (node (ref "R2") (pin "2") (pinfunction "2_2") (pintype "passive"))
    )
    (net (code "50") (name "Net-(M1-ISENB)") (class "Default")
      (node (ref "M1") (pin "9") (pinfunction "ISENB_9") (pintype "bidirectional"))
      (node (ref "R3") (pin "2") (pinfunction "2_2") (pintype "passive"))
      (node (ref "R4") (pin "2") (pinfunction "2_2") (pintype "passive"))
    )
    (net (code "51") (name "Net-(M1-VCP)") (class "Default")
      (node (ref "C3") (pin "2") (pinfunction "2_2") (pintype "passive"))
      (node (ref "M1") (pin "3") (pinfunction "VCP_3") (pintype "output"))
    )
    (net (code "52") (name "Net-(M1-~{HOME})") (class "Default")
      (node (ref "ACT(DEC)") (pin "C") (pinfunction "C_C") (pintype "passive"))
      (node (ref "M1") (pin "27") (pinfunction "~{HOME}_27") (pintype "output"))
    )
    (net (code "53") (name "Net-(M2-AOUT1)") (class "Default")
      (node (ref "M2") (pin "5") (pinfunction "AOUT1_5") (pintype "output"))
      (node (ref "MOTOR2") (pin "4") (pinfunction "4_4") (pintype "passive"))
      (node (ref "RA") (pin "5") (pinfunction "5_5") (pintype "passive"))
    )
    (net (code "54") (name "Net-(M2-AOUT2)") (class "Default")
      (node (ref "M2") (pin "7") (pinfunction "AOUT2_7") (pintype "output"))
      (node (ref "MOTOR2") (pin "3") (pinfunction "3_3") (pintype "passive"))
      (node (ref "RA") (pin "2") (pinfunction "2_2") (pintype "passive"))
    )
    (net (code "55") (name "Net-(M2-AVREF)") (class "Default")
      (node (ref "C6") (pin "2") (pinfunction "2_2") (pintype "passive"))
      (node (ref "M2") (pin "12") (pinfunction "AVREF_12") (pintype "input"))
      (node (ref "M2") (pin "13") (pinfunction "BVREF_13") (pintype "input"))
      (node (ref "M2") (pin "15") (pinfunction "V3P3_15") (pintype "output"))
      (node (ref "M2") (pin "19") (pinfunction "DECAY_19") (pintype "input"))
    )
    (net (code "56") (name "Net-(M2-BOUT1)") (class "Default")
      (node (ref "M2") (pin "10") (pinfunction "BOUT1_10") (pintype "output"))
      (node (ref "MOTOR2") (pin "1") (pinfunction "1_1") (pintype "passive"))
      (node (ref "RA") (pin "3") (pinfunction "3_3") (pintype "passive"))
    )
    (net (code "57") (name "Net-(M2-BOUT2)") (class "Default")
      (node (ref "M2") (pin "8") (pinfunction "BOUT2_8") (pintype "output"))
      (node (ref "MOTOR2") (pin "2") (pinfunction "2_2") (pintype "passive"))
      (node (ref "RA") (pin "4") (pinfunction "4_4") (pintype "passive"))
    )
    (net (code "58") (name "Net-(M2-CP1)") (class "Default")
      (node (ref "C5") (pin "1") (pinfunction "1_1") (pintype "passive"))
      (node (ref "M2") (pin "1") (pinfunction "CP1_1") (pintype "passive"))
    )
    (net (code "59") (name "Net-(M2-CP2)") (class "Default")
      (node (ref "C5") (pin "2") (pinfunction "2_2") (pintype "passive"))
      (node (ref "M2") (pin "2") (pinfunction "CP2_2") (pintype "passive"))
    )
    (net (code "60") (name "Net-(M2-ISENA)") (class "Default")
      (node (ref "M2") (pin "6") (pinfunction "ISENA_6") (pintype "bidirectional"))
      (node (ref "R7") (pin "2") (pinfunction "2_2") (pintype "passive"))
      (node (ref "R8") (pin "2") (pinfunction "2_2") (pintype "passive"))
    )
    (net (code "61") (name "Net-(M2-ISENB)") (class "Default")
      (node (ref "M2") (pin "9") (pinfunction "ISENB_9") (pintype "bidirectional"))
      (node (ref "R10") (pin "2") (pinfunction "2_2") (pintype "passive"))
      (node (ref "R9") (pin "2") (pinfunction "2_2") (pintype "passive"))
    )
    (net (code "62") (name "Net-(M2-VCP)") (class "Default")
      (node (ref "C7") (pin "2") (pinfunction "2_2") (pintype "passive"))
      (node (ref "M2") (pin "3") (pinfunction "VCP_3") (pintype "output"))
    )
    (net (code "63") (name "Net-(M2-~{HOME})") (class "Default")
      (node (ref "ACT(RA)") (pin "C") (pinfunction "C_C") (pintype "passive"))
      (node (ref "M2") (pin "27") (pinfunction "~{HOME}_27") (pintype "output"))
    )
    (net (code "64") (name "Net-(POWER-PadA)") (class "Default")
      (node (ref "POWER") (pin "A") (pinfunction "A_A") (pintype "passive"))
      (node (ref "R14") (pin "2") (pinfunction "2_2") (pintype "passive"))
    )
    (net (code "65") (name "Net-(R13-Pad2)") (class "Default")
      (node (ref "R13") (pin "2") (pinfunction "2_2") (pintype "passive"))
      (node (ref "STATUS") (pin "A") (pinfunction "A_A") (pintype "passive"))
    )
    (net (code "66") (name "Net-(R19-Pad1)") (class "Default")
      (node (ref "R19") (pin "1") (pinfunction "1_1") (pintype "passive"))
      (node (ref "USB") (pin "A") (pinfunction "A_A") (pintype "passive"))
    )
    (net (code "67") (name "V+") (class "Default")
      (node (ref "C10") (pin "1") (pinfunction "1_1") (pintype "passive"))
      (node (ref "C4") (pin "+") (pinfunction "+_+") (pintype "passive"))
      (node (ref "C8") (pin "+") (pinfunction "+_+") (pintype "passive"))
      (node (ref "D1") (pin "C") (pinfunction "C_C") (pintype "passive"))
      (node (ref "IC3") (pin "2") (pinfunction "IN_2") (pintype "input"))
      (node (ref "M1") (pin "11") (pinfunction "VMB_11") (pintype "power_in"))
      (node (ref "M1") (pin "4") (pinfunction "VMA_4") (pintype "power_in"))
      (node (ref "M2") (pin "11") (pinfunction "VMB_11") (pintype "power_in"))
      (node (ref "M2") (pin "4") (pinfunction "VMA_4") (pintype "power_in"))
    )
    (net (code "68") (name "unconnected-(DEC-Pad1)") (class "Default")
      (node (ref "DEC") (pin "1") (pinfunction "1_1") (pintype "passive"))
    )
    (net (code "69") (name "unconnected-(DEC-Pad6)") (class "Default")
      (node (ref "DEC") (pin "6") (pinfunction "6_6") (pintype "passive"))
    )
    (net (code "70") (name "unconnected-(IC1-PA4{slash}AD4{slash}PCINT4-Pad33)") (class "Default")
      (node (ref "IC1") (pin "33") (pinfunction "PA4/AD4/PCINT4_33") (pintype "bidirectional"))
    )
    (net (code "71") (name "unconnected-(IC1-PA5{slash}AD5{slash}PCINT5-Pad32)") (class "Default")
      (node (ref "IC1") (pin "32") (pinfunction "PA5/AD5/PCINT5_32") (pintype "bidirectional"))
    )
    (net (code "72") (name "unconnected-(IC1-PA6{slash}AD6{slash}PCINT6-Pad31)") (class "Default")
      (node (ref "IC1") (pin "31") (pinfunction "PA6/AD6/PCINT6_31") (pintype "bidirectional"))
    )
    (net (code "73") (name "unconnected-(IC1-PA7{slash}AD7{slash}PCINT7-Pad30)") (class "Default")
      (node (ref "IC1") (pin "30") (pinfunction "PA7/AD7/PCINT7_30") (pintype "bidirectional"))
    )
    (net (code "74") (name "unconnected-(IC1-PB1{slash}T1{slash}OC2-Pad41)") (class "Default")
      (node (ref "IC1") (pin "41") (pinfunction "PB1/T1/OC2_41") (pintype "bidirectional"))
    )
    (net (code "75") (name "unconnected-(IC1-PB4{slash}OC3B{slash}~{SS}-Pad44)") (class "Default")
      (node (ref "IC1") (pin "44") (pinfunction "PB4/OC3B/~{SS}_44") (pintype "bidirectional"))
    )
    (net (code "76") (name "unconnected-(IC1-PC0{slash}A8{slash}PCINT8-Pad18)") (class "Default")
      (node (ref "IC1") (pin "18") (pinfunction "PC0/A8/PCINT8_18") (pintype "bidirectional"))
    )
    (net (code "77") (name "unconnected-(IC1-PC1{slash}A9{slash}PCINT9-Pad19)") (class "Default")
      (node (ref "IC1") (pin "19") (pinfunction "PC1/A9/PCINT9_19") (pintype "bidirectional"))
    )
    (net (code "78") (name "unconnected-(IC1-PC2{slash}A10{slash}PCINT10-Pad20)") (class "Default")
      (node (ref "IC1") (pin "20") (pinfunction "PC2/A10/PCINT10_20") (pintype "bidirectional"))
    )
    (net (code "79") (name "unconnected-(IC1-PC3{slash}A11{slash}PCINT11-Pad21)") (class "Default")
      (node (ref "IC1") (pin "21") (pinfunction "PC3/A11/PCINT11_21") (pintype "bidirectional"))
    )
    (net (code "80") (name "unconnected-(IC1-PC4{slash}A12{slash}TCK{slash}PCINT12-Pad22)") (class "Default")
      (node (ref "IC1") (pin "22") (pinfunction "PC4/A12/TCK/PCINT12_22") (pintype "bidirectional"))
    )
    (net (code "81") (name "unconnected-(IC1-PC5{slash}A13{slash}TMS{slash}PCINT13-Pad23)") (class "Default")
      (node (ref "IC1") (pin "23") (pinfunction "PC5/A13/TMS/PCINT13_23") (pintype "bidirectional"))
    )
    (net (code "82") (name "unconnected-(IC1-PC6{slash}A14{slash}TDO{slash}PCINT14-Pad24)") (class "Default")
      (node (ref "IC1") (pin "24") (pinfunction "PC6/A14/TDO/PCINT14_24") (pintype "bidirectional"))
    )
    (net (code "83") (name "unconnected-(IC1-PC7{slash}A15{slash}TDI{slash}PCINT15-Pad25)") (class "Default")
      (node (ref "IC1") (pin "25") (pinfunction "PC7/A15/TDI/PCINT15_25") (pintype "bidirectional"))
    )
    (net (code "84") (name "unconnected-(IC1-PE0{slash}ICP1{slash}INT2-Pad29)") (class "Default")
      (node (ref "IC1") (pin "29") (pinfunction "PE0/ICP1/INT2_29") (pintype "bidirectional"))
    )
    (net (code "85") (name "unconnected-(IC1-PE1{slash}ALE-Pad27)") (class "Default")
      (node (ref "IC1") (pin "27") (pinfunction "PE1/ALE_27") (pintype "bidirectional"))
    )
    (net (code "86") (name "unconnected-(IC2-RB4{slash}AN10{slash}SDI{slash}SDA-Pad13)") (class "Default")
      (node (ref "IC2") (pin "13") (pinfunction "RB4/AN10/SDI/SDA_13") (pintype "bidirectional"))
    )
    (net (code "87") (name "unconnected-(IC2-RB6{slash}SCK{slash}SCL-Pad11)") (class "Default")
      (node (ref "IC2") (pin "11") (pinfunction "RB6/SCK/SCL_11") (pintype "bidirectional"))
    )
    (net (code "88") (name "unconnected-(IC2-RC1{slash}AN5{slash}C12IN1-{slash}INT1{slash}VREF--Pad15)") (class "Default")
      (node (ref "IC2") (pin "15") (pinfunction "RC1/AN5/C12IN1-/INT1/VREF-_15") (pintype "bidirectional"))
    )
    (net (code "89") (name "unconnected-(IC2-RC2{slash}AN6{slash}P1D{slash}C12IN2-{slash}CVREF{slash}INT2-Pad14)") (class "Default")
      (node (ref "IC2") (pin "14") (pinfunction "RC2/AN6/P1D/C12IN2-/CVREF/INT2_14") (pintype "bidirectional"))
    )
    (net (code "90") (name "unconnected-(IC2-RC3{slash}AN7{slash}P1C{slash}C12IN3-{slash}PGM-Pad7)") (class "Default")
      (node (ref "IC2") (pin "7") (pinfunction "RC3/AN7/P1C/C12IN3-/PGM_7") (pintype "bidirectional"))
    )
    (net (code "91") (name "unconnected-(IC2-RC4{slash}P1B{slash}C12OUT{slash}SRQ-Pad6)") (class "Default")
      (node (ref "IC2") (pin "6") (pinfunction "RC4/P1B/C12OUT/SRQ_6") (pintype "bidirectional"))
    )
    (net (code "92") (name "unconnected-(IC2-RC5{slash}CCP1{slash}P1A{slash}T0CKI-Pad5)") (class "Default")
      (node (ref "IC2") (pin "5") (pinfunction "RC5/CCP1/P1A/T0CKI_5") (pintype "bidirectional"))
    )
    (net (code "93") (name "unconnected-(IC2-RC6{slash}AN8{slash}~{SS{slash}T13CKI{slash}T1OSCI}-Pad8)") (class "Default")
      (node (ref "IC2") (pin "8") (pinfunction "RC6/AN8/~{SS/T13CKI/T1OSCI}_8") (pintype "bidirectional"))
    )
    (net (code "94") (name "unconnected-(M1-N{slash}C-Pad23)") (class "Default")
      (node (ref "M1") (pin "23") (pinfunction "N/C_23") (pintype "no_connect"))
    )
    (net (code "95") (name "unconnected-(M2-N{slash}C-Pad23)") (class "Default")
      (node (ref "M2") (pin "23") (pinfunction "N/C_23") (pintype "no_connect"))
    )
    (net (code "96") (name "unconnected-(RA-Pad1)") (class "Default")
      (node (ref "RA") (pin "1") (pinfunction "1_1") (pintype "passive"))
    )
    (net (code "97") (name "unconnected-(RA-Pad6)") (class "Default")
      (node (ref "RA") (pin "6") (pinfunction "6_6") (pintype "passive"))
    )
    (net (code "98") (name "unconnected-(USB->-PadID)") (class "Default")
      (node (ref "USB->") (pin "ID") (pinfunction "ID_ID") (pintype "bidirectional"))
    )
  )
)
